# stc15_dev.net
KiCad netlist of a schematic drawn in EAGLE
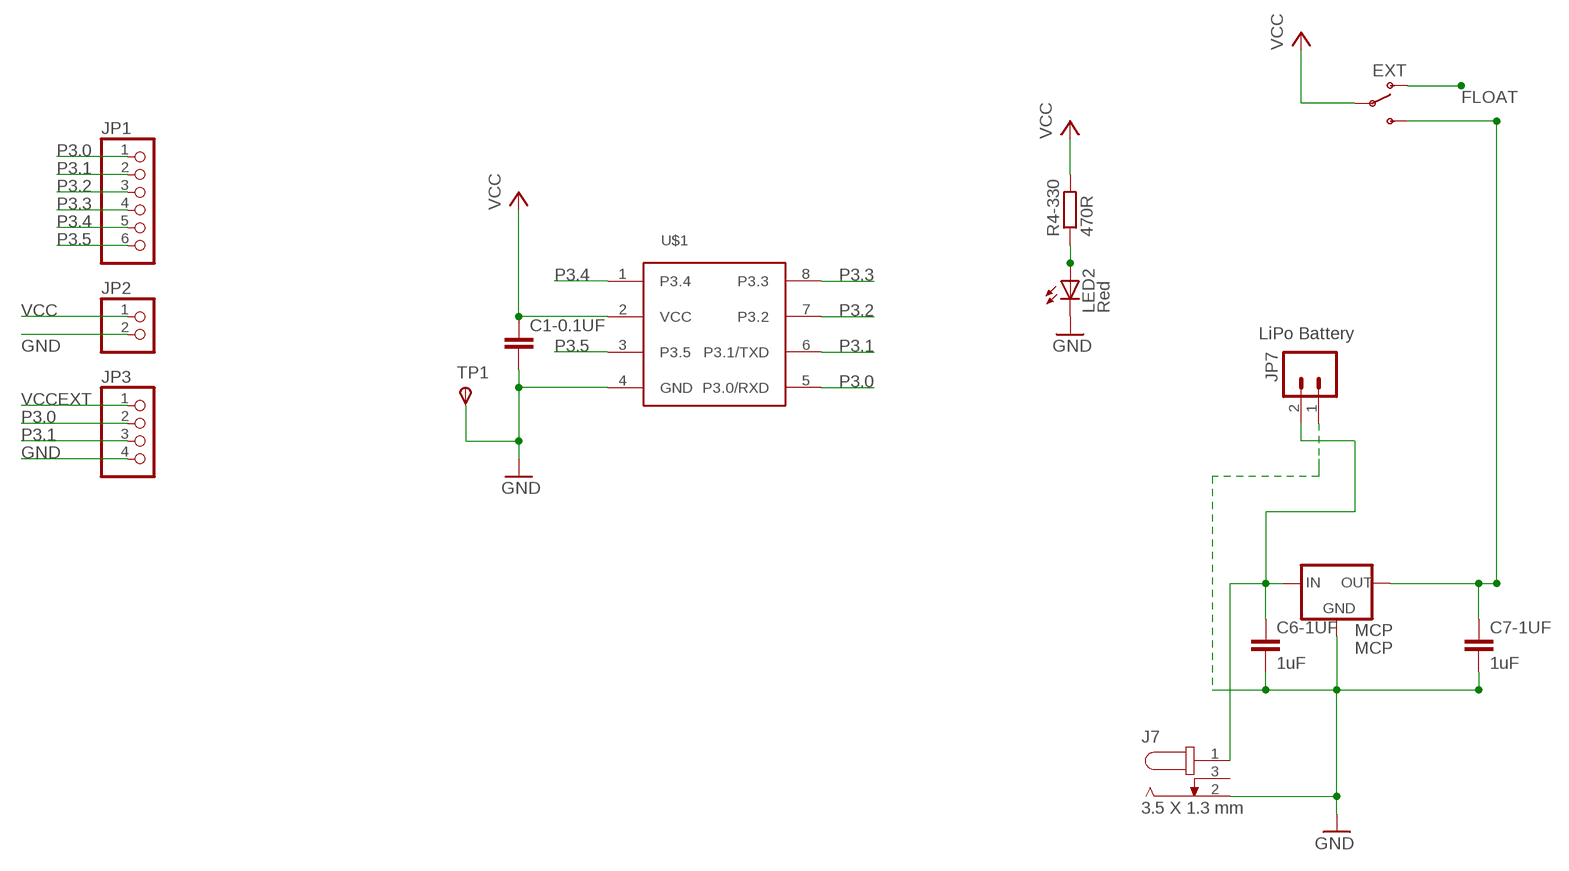
[diagram p0: schematic, sheet 1]

(export (version "E")
  (design (tool "Eeschema 10.0.6"))
  (components
    (comp (ref "C1-0.1UF")
      (value "C-EU025-025X050")
      (footprint "eagle-import:C025-025X050")
      (libsource (lib "eagle-import") (part "C-EU025-025X050"))
    )
    (comp (ref "C6-1UF")
      (value "1uF")
      (footprint "eagle-import:C025-025X050")
      (libsource (lib "eagle-import") (part "C-EU025-025X050"))
    )
    (comp (ref "C7-1UF")
      (value "1uF")
      (footprint "eagle-import:C025-025X050")
      (libsource (lib "eagle-import") (part "C-EU025-025X050"))
    )
    (comp (ref "J7")
      (value "3.5 X 1.3 mm")
      (footprint "eagle-import:3.5X1.3MM_DC_JACK")
      (libsource (lib "eagle-import") (part "DC_JACK_3.5X1.3MM"))
    )
    (comp (ref "JP1")
      (value "PINHD-1X6")
      (footprint "eagle-import:1X06")
      (libsource (lib "eagle-import") (part "PINHD-1X6"))
    )
    (comp (ref "JP2")
      (value "PINHD-1X2")
      (footprint "eagle-import:1X02")
      (libsource (lib "eagle-import") (part "PINHD-1X2"))
    )
    (comp (ref "JP3")
      (value "PINHD-1X4")
      (footprint "eagle-import:1X04")
      (libsource (lib "eagle-import") (part "PINHD-1X4"))
    )
    (comp (ref "JP7")
      (value "LiPo Battery")
      (footprint "eagle-import:JST-2-PTH")
      (libsource (lib "eagle-import") (part "M02JST-PTH-2"))
    )
    (comp (ref "LED2")
      (value "Red")
      (footprint "eagle-import:LED3MM")
      (libsource (lib "eagle-import") (part "LED3MM"))
    )
    (comp (ref "MCP")
      (value "MCP")
      (footprint "eagle-import:TO92-")
      (libsource (lib "eagle-import") (part "MCP1700TO-92"))
    )
    (comp (ref "ON")
      (value "EXT")
      (footprint "eagle-import:SWITCH-SPDT")
      (libsource (lib "eagle-import") (part "SWITCH-SPSTPTH"))
    )
    (comp (ref "R4-330")
      (value "470R")
      (footprint "eagle-import:0204_7")
      (libsource (lib "eagle-import") (part "R-EU_0204/7"))
    )
    (comp (ref "TP1")
      (value "TPSTP20R")
      (footprint "eagle-import:TP20R")
      (libsource (lib "eagle-import") (part "TPSTP20R"))
    )
    (comp (ref "U$1")
      (value "STC15F/L10XDIP")
      (footprint "eagle-import:DIL4")
      (libsource (lib "eagle-import") (part "STC15F/L10XDIP"))
    )
  )
  (nets
    (net (code "1") (name "/FLOAT") (class "Default")
      (node (ref "ON") (pin "1") (pinfunction "O_1") (pintype "passive"))
    )
    (net (code "2") (name "/P3.0") (class "Default")
      (node (ref "JP1") (pin "1") (pinfunction "1_1") (pintype "passive"))
      (node (ref "JP3") (pin "2") (pinfunction "2_2") (pintype "passive"))
      (node (ref "U$1") (pin "5") (pinfunction "P3.0/RXD_5") (pintype "bidirectional"))
    )
    (net (code "3") (name "/P3.1") (class "Default")
      (node (ref "JP1") (pin "2") (pinfunction "2_2") (pintype "passive"))
      (node (ref "JP3") (pin "3") (pinfunction "3_3") (pintype "passive"))
      (node (ref "U$1") (pin "6") (pinfunction "P3.1/TXD_6") (pintype "bidirectional"))
    )
    (net (code "4") (name "/P3.2") (class "Default")
      (node (ref "JP1") (pin "3") (pinfunction "3_3") (pintype "passive"))
      (node (ref "U$1") (pin "7") (pinfunction "P3.2_7") (pintype "bidirectional"))
    )
    (net (code "5") (name "/P3.3") (class "Default")
      (node (ref "JP1") (pin "4") (pinfunction "4_4") (pintype "passive"))
      (node (ref "U$1") (pin "8") (pinfunction "P3.3_8") (pintype "bidirectional"))
    )
    (net (code "6") (name "/P3.4") (class "Default")
      (node (ref "JP1") (pin "5") (pinfunction "5_5") (pintype "passive"))
      (node (ref "U$1") (pin "1") (pinfunction "P3.4_1") (pintype "bidirectional"))
    )
    (net (code "7") (name "/P3.5") (class "Default")
      (node (ref "JP1") (pin "6") (pinfunction "6_6") (pintype "passive"))
      (node (ref "U$1") (pin "3") (pinfunction "P3.5_3") (pintype "bidirectional"))
    )
    (net (code "8") (name "/VCCEXT") (class "Default")
      (node (ref "C6-1UF") (pin "1") (pinfunction "1_1") (pintype "passive"))
      (node (ref "J7") (pin "1") (pinfunction "1_1") (pintype "passive"))
      (node (ref "JP3") (pin "1") (pinfunction "1_1") (pintype "passive"))
      (node (ref "JP7") (pin "2") (pinfunction "2_2") (pintype "passive"))
      (node (ref "MCP") (pin "2") (pinfunction "IN_2") (pintype "input"))
    )
    (net (code "9") (name "GND") (class "Default")
      (node (ref "C1-0.1UF") (pin "2") (pinfunction "2_2") (pintype "passive"))
      (node (ref "C6-1UF") (pin "2") (pinfunction "2_2") (pintype "passive"))
      (node (ref "C7-1UF") (pin "2") (pinfunction "2_2") (pintype "passive"))
      (node (ref "J7") (pin "2") (pinfunction "2_2") (pintype "passive"))
      (node (ref "JP2") (pin "2") (pinfunction "2_2") (pintype "passive"))
      (node (ref "JP3") (pin "4") (pinfunction "4_4") (pintype "passive"))
      (node (ref "JP7") (pin "1") (pinfunction "1_1") (pintype "passive"))
      (node (ref "LED2") (pin "K") (pinfunction "C_K") (pintype "passive"))
      (node (ref "MCP") (pin "3") (pinfunction "GND_3") (pintype "input"))
      (node (ref "TP1") (pin "TP") (pinfunction "PP_TP") (pintype "input"))
      (node (ref "U$1") (pin "4") (pinfunction "GND_4") (pintype "power_in"))
    )
    (net (code "10") (name "Net-(LED2-PadA)") (class "Default")
      (node (ref "LED2") (pin "A") (pinfunction "A_A") (pintype "passive"))
      (node (ref "R4-330") (pin "1") (pinfunction "1_1") (pintype "passive"))
    )
    (net (code "11") (name "Net-(MCP-OUT)") (class "Default")
      (node (ref "C7-1UF") (pin "1") (pinfunction "1_1") (pintype "passive"))
      (node (ref "MCP") (pin "1") (pinfunction "OUT_1") (pintype "passive"))
      (node (ref "ON") (pin "3") (pinfunction "S_3") (pintype "passive"))
    )
    (net (code "12") (name "VCC") (class "Default")
      (node (ref "C1-0.1UF") (pin "1") (pinfunction "1_1") (pintype "passive"))
      (node (ref "JP2") (pin "1") (pinfunction "1_1") (pintype "passive"))
      (node (ref "ON") (pin "2") (pinfunction "P_2") (pintype "passive"))
      (node (ref "R4-330") (pin "2") (pinfunction "2_2") (pintype "passive"))
      (node (ref "U$1") (pin "2") (pinfunction "VCC_2") (pintype "power_in"))
    )
    (net (code "13") (name "unconnected-(J7-Pad3)") (class "Default")
      (node (ref "J7") (pin "3") (pinfunction "3_3") (pintype "passive"))
    )
  )
)
